# LoRaWAN_FW_RevB.net
KiCad netlist of a schematic drawn in EAGLE
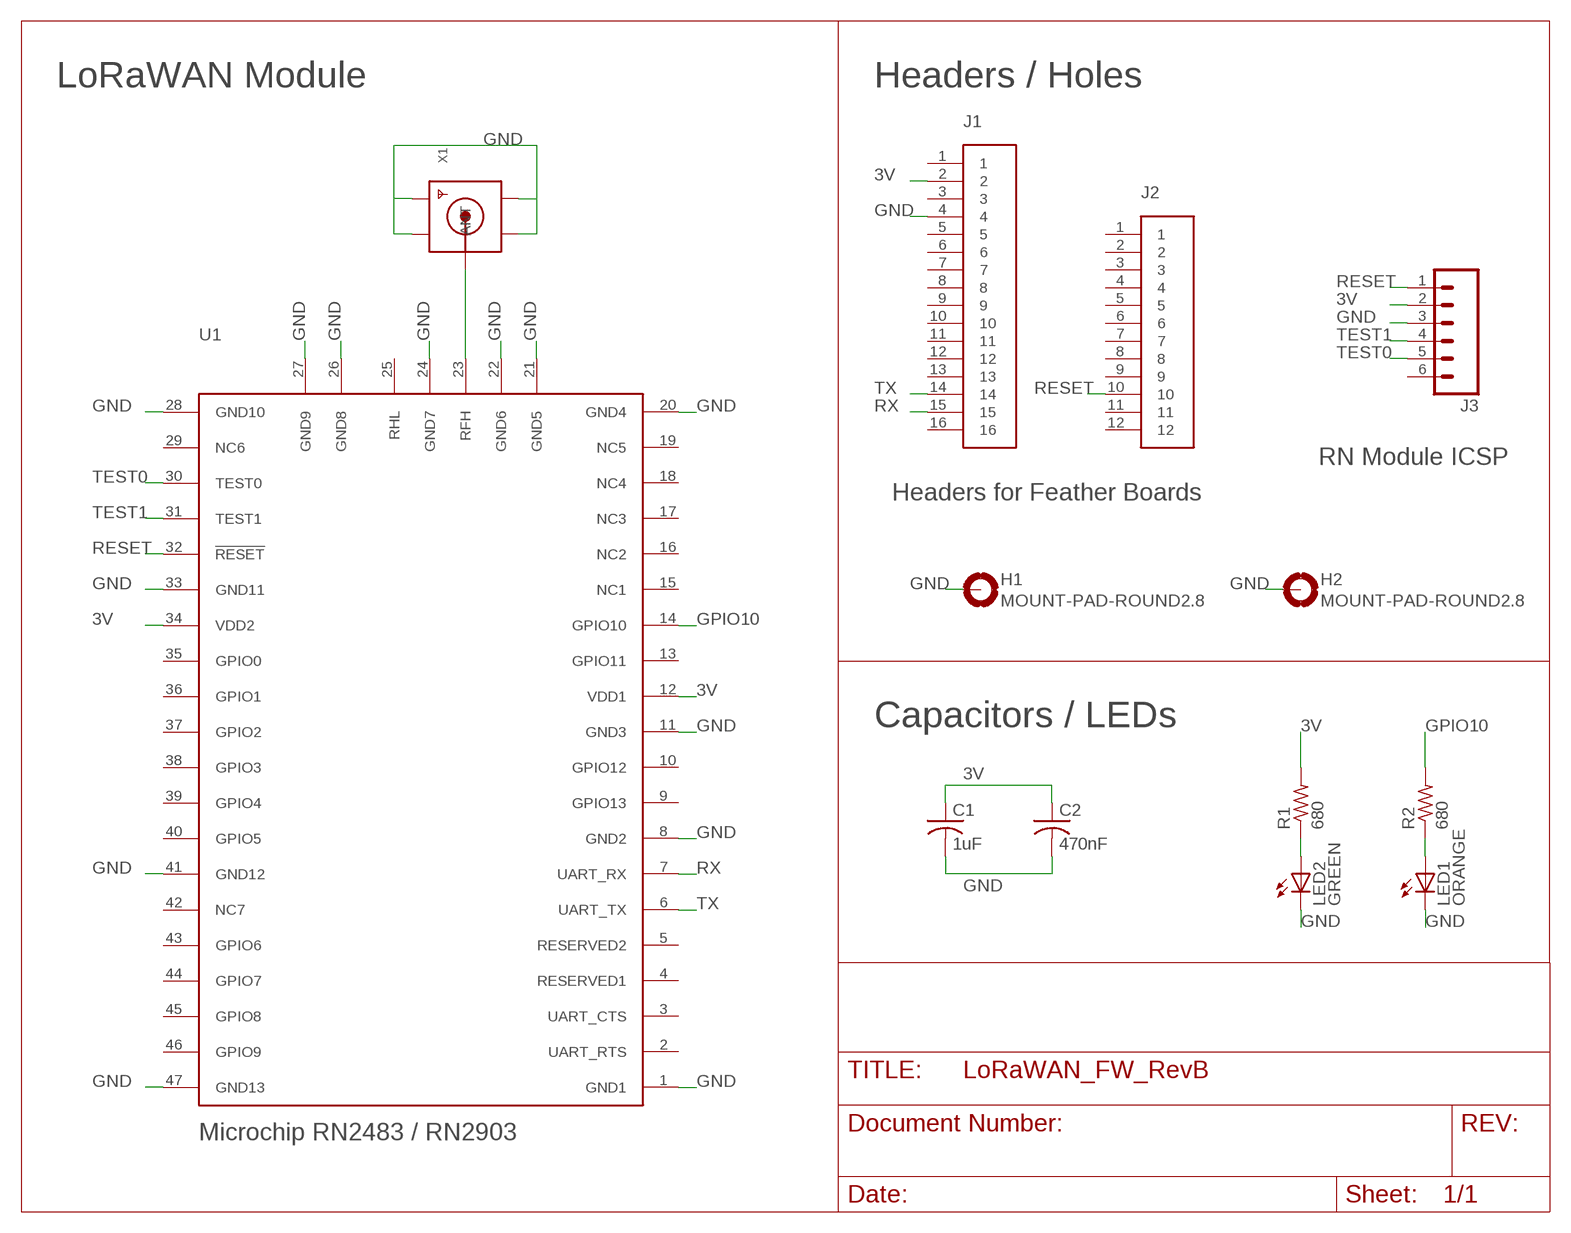
[diagram p0: schematic, sheet 1]

(export (version "E")
  (design (tool "Eeschema 10.0.6"))
  (components
    (comp (ref "C1")
      (value "1uF")
      (footprint "eagle-import:C0603")
      (libsource (lib "eagle-import") (part "C-USC0603"))
    )
    (comp (ref "C2")
      (value "470nF")
      (footprint "eagle-import:C0603")
      (libsource (lib "eagle-import") (part "C-USC0603"))
    )
    (comp (ref "H1")
      (value "MOUNT-PAD-ROUND2.8")
      (footprint "eagle-import:2,8-PAD")
      (libsource (lib "eagle-import") (part "MOUNT-PAD-ROUND2.8"))
    )
    (comp (ref "H2")
      (value "MOUNT-PAD-ROUND2.8")
      (footprint "eagle-import:2,8-PAD")
      (libsource (lib "eagle-import") (part "MOUNT-PAD-ROUND2.8"))
    )
    (comp (ref "J1")
      (value "1X16_SMD_HEADER")
      (footprint "eagle-import:1X16_SMD_HEADER")
      (libsource (lib "eagle-import") (part "1X16_SMD_HEADER"))
    )
    (comp (ref "J2")
      (value "1X12_SMD_HEADER")
      (footprint "eagle-import:1X12_SMD_HEADER")
      (libsource (lib "eagle-import") (part "1X12_SMD_HEADER"))
    )
    (comp (ref "J3")
      (value "M06SILK_FEMALE_PTH")
      (footprint "eagle-import:1X06")
      (libsource (lib "eagle-import") (part "M06SILK_FEMALE_PTH"))
    )
    (comp (ref "LED1")
      (value "ORANGE")
      (footprint "eagle-import:CHIPLED_0805")
      (libsource (lib "eagle-import") (part "LEDCHIPLED_0805"))
    )
    (comp (ref "LED2")
      (value "GREEN")
      (footprint "eagle-import:CHIPLED_0805")
      (libsource (lib "eagle-import") (part "LEDCHIPLED_0805"))
    )
    (comp (ref "R1")
      (value "680")
      (footprint "eagle-import:R0603")
      (libsource (lib "eagle-import") (part "R-US_R0603"))
    )
    (comp (ref "R2")
      (value "680")
      (footprint "eagle-import:R0603")
      (libsource (lib "eagle-import") (part "R-US_R0603"))
    )
    (comp (ref "U1")
      (value "RN2483/RN2903")
      (footprint "eagle-import:RN2483_RN2903")
      (libsource (lib "eagle-import") (part "RN2483/RN2903"))
    )
    (comp (ref "X1")
      (value "SMACONNECTOR_EDGE")
      (footprint "eagle-import:SMA_EDGELAUNCH")
      (libsource (lib "eagle-import") (part "SMACONNECTOR_EDGE"))
    )
  )
  (nets
    (net (code "1") (name "/3V") (class "Default")
      (node (ref "C1") (pin "1") (pinfunction "1_1") (pintype "passive"))
      (node (ref "C2") (pin "1") (pinfunction "1_1") (pintype "passive"))
      (node (ref "J1") (pin "2") (pinfunction "2_2") (pintype "bidirectional"))
      (node (ref "J3") (pin "2") (pinfunction "2_2") (pintype "passive"))
      (node (ref "R1") (pin "2") (pinfunction "2_2") (pintype "passive"))
      (node (ref "U1") (pin "12") (pinfunction "VDD1_12") (pintype "bidirectional"))
      (node (ref "U1") (pin "34") (pinfunction "VDD2_34") (pintype "bidirectional"))
    )
    (net (code "2") (name "/GND") (class "Default")
      (node (ref "C1") (pin "2") (pinfunction "2_2") (pintype "passive"))
      (node (ref "C2") (pin "2") (pinfunction "2_2") (pintype "passive"))
      (node (ref "H1") (pin "B2,8") (pinfunction "MOUNT_B2,8") (pintype "passive"))
      (node (ref "H2") (pin "B2,8") (pinfunction "MOUNT_B2,8") (pintype "passive"))
      (node (ref "J1") (pin "4") (pinfunction "4_4") (pintype "bidirectional"))
      (node (ref "J3") (pin "3") (pinfunction "3_3") (pintype "passive"))
      (node (ref "LED1") (pin "C") (pinfunction "C_C") (pintype "passive"))
      (node (ref "LED2") (pin "C") (pinfunction "C_C") (pintype "passive"))
      (node (ref "U1") (pin "1") (pinfunction "GND1_1") (pintype "bidirectional"))
      (node (ref "U1") (pin "11") (pinfunction "GND3_11") (pintype "bidirectional"))
      (node (ref "U1") (pin "20") (pinfunction "GND4_20") (pintype "bidirectional"))
      (node (ref "U1") (pin "21") (pinfunction "GND5_21") (pintype "bidirectional"))
      (node (ref "U1") (pin "22") (pinfunction "GND6_22") (pintype "bidirectional"))
      (node (ref "U1") (pin "24") (pinfunction "GND7_24") (pintype "bidirectional"))
      (node (ref "U1") (pin "26") (pinfunction "GND8_26") (pintype "bidirectional"))
      (node (ref "U1") (pin "27") (pinfunction "GND9_27") (pintype "bidirectional"))
      (node (ref "U1") (pin "28") (pinfunction "GND10_28") (pintype "bidirectional"))
      (node (ref "U1") (pin "33") (pinfunction "GND11_33") (pintype "bidirectional"))
      (node (ref "U1") (pin "41") (pinfunction "GND12_41") (pintype "bidirectional"))
      (node (ref "U1") (pin "47") (pinfunction "GND13_47") (pintype "bidirectional"))
      (node (ref "U1") (pin "8") (pinfunction "GND2_8") (pintype "bidirectional"))
      (node (ref "X1") (pin "GND@1") (pinfunction "GND4_GND@1") (pintype "power_in"))
      (node (ref "X1") (pin "GND@2") (pinfunction "GND3_GND@2") (pintype "power_in"))
      (node (ref "X1") (pin "GND@3") (pinfunction "GND2_GND@3") (pintype "power_in"))
      (node (ref "X1") (pin "GND@4") (pinfunction "GND1_GND@4") (pintype "power_in"))
    )
    (net (code "3") (name "/GPIO10") (class "Default")
      (node (ref "R2") (pin "2") (pinfunction "2_2") (pintype "passive"))
      (node (ref "U1") (pin "14") (pinfunction "GPIO10_14") (pintype "bidirectional"))
    )
    (net (code "4") (name "/RESET") (class "Default")
      (node (ref "J2") (pin "10") (pinfunction "10_10") (pintype "bidirectional"))
      (node (ref "J3") (pin "1") (pinfunction "1_1") (pintype "passive"))
      (node (ref "U1") (pin "32") (pinfunction "~{RESET}_32") (pintype "bidirectional"))
    )
    (net (code "5") (name "/RX") (class "Default")
      (node (ref "J1") (pin "15") (pinfunction "15_15") (pintype "bidirectional"))
      (node (ref "U1") (pin "7") (pinfunction "UART_RX_7") (pintype "bidirectional"))
    )
    (net (code "6") (name "/TEST0") (class "Default")
      (node (ref "J3") (pin "5") (pinfunction "5_5") (pintype "passive"))
      (node (ref "U1") (pin "30") (pinfunction "TEST0_30") (pintype "bidirectional"))
    )
    (net (code "7") (name "/TEST1") (class "Default")
      (node (ref "J3") (pin "4") (pinfunction "4_4") (pintype "passive"))
      (node (ref "U1") (pin "31") (pinfunction "TEST1_31") (pintype "bidirectional"))
    )
    (net (code "8") (name "/TX") (class "Default")
      (node (ref "J1") (pin "14") (pinfunction "14_14") (pintype "bidirectional"))
      (node (ref "U1") (pin "6") (pinfunction "UART_TX_6") (pintype "bidirectional"))
    )
    (net (code "9") (name "Net-(LED1-PadA)") (class "Default")
      (node (ref "LED1") (pin "A") (pinfunction "A_A") (pintype "passive"))
      (node (ref "R2") (pin "1") (pinfunction "1_1") (pintype "passive"))
    )
    (net (code "10") (name "Net-(LED2-PadA)") (class "Default")
      (node (ref "LED2") (pin "A") (pinfunction "A_A") (pintype "passive"))
      (node (ref "R1") (pin "1") (pinfunction "1_1") (pintype "passive"))
    )
    (net (code "11") (name "Net-(U1-RFH)") (class "Default")
      (node (ref "U1") (pin "23") (pinfunction "RFH_23") (pintype "bidirectional"))
      (node (ref "X1") (pin "P") (pinfunction "ANT_P") (pintype "bidirectional"))
    )
    (net (code "12") (name "unconnected-(J1-Pad1)") (class "Default")
      (node (ref "J1") (pin "1") (pinfunction "1_1") (pintype "bidirectional"))
    )
    (net (code "13") (name "unconnected-(J1-Pad3)") (class "Default")
      (node (ref "J1") (pin "3") (pinfunction "3_3") (pintype "bidirectional"))
    )
    (net (code "14") (name "unconnected-(J1-Pad5)") (class "Default")
      (node (ref "J1") (pin "5") (pinfunction "5_5") (pintype "bidirectional"))
    )
    (net (code "15") (name "unconnected-(J1-Pad6)") (class "Default")
      (node (ref "J1") (pin "6") (pinfunction "6_6") (pintype "bidirectional"))
    )
    (net (code "16") (name "unconnected-(J1-Pad7)") (class "Default")
      (node (ref "J1") (pin "7") (pinfunction "7_7") (pintype "bidirectional"))
    )
    (net (code "17") (name "unconnected-(J1-Pad8)") (class "Default")
      (node (ref "J1") (pin "8") (pinfunction "8_8") (pintype "bidirectional"))
    )
    (net (code "18") (name "unconnected-(J1-Pad9)") (class "Default")
      (node (ref "J1") (pin "9") (pinfunction "9_9") (pintype "bidirectional"))
    )
    (net (code "19") (name "unconnected-(J1-Pad10)") (class "Default")
      (node (ref "J1") (pin "10") (pinfunction "10_10") (pintype "bidirectional"))
    )
    (net (code "20") (name "unconnected-(J1-Pad11)") (class "Default")
      (node (ref "J1") (pin "11") (pinfunction "11_11") (pintype "bidirectional"))
    )
    (net (code "21") (name "unconnected-(J1-Pad12)") (class "Default")
      (node (ref "J1") (pin "12") (pinfunction "12_12") (pintype "bidirectional"))
    )
    (net (code "22") (name "unconnected-(J1-Pad13)") (class "Default")
      (node (ref "J1") (pin "13") (pinfunction "13_13") (pintype "bidirectional"))
    )
    (net (code "23") (name "unconnected-(J1-Pad16)") (class "Default")
      (node (ref "J1") (pin "16") (pinfunction "16_16") (pintype "bidirectional"))
    )
    (net (code "24") (name "unconnected-(J2-Pad1)") (class "Default")
      (node (ref "J2") (pin "1") (pinfunction "1_1") (pintype "bidirectional"))
    )
    (net (code "25") (name "unconnected-(J2-Pad2)") (class "Default")
      (node (ref "J2") (pin "2") (pinfunction "2_2") (pintype "bidirectional"))
    )
    (net (code "26") (name "unconnected-(J2-Pad3)") (class "Default")
      (node (ref "J2") (pin "3") (pinfunction "3_3") (pintype "bidirectional"))
    )
    (net (code "27") (name "unconnected-(J2-Pad4)") (class "Default")
      (node (ref "J2") (pin "4") (pinfunction "4_4") (pintype "bidirectional"))
    )
    (net (code "28") (name "unconnected-(J2-Pad5)") (class "Default")
      (node (ref "J2") (pin "5") (pinfunction "5_5") (pintype "bidirectional"))
    )
    (net (code "29") (name "unconnected-(J2-Pad6)") (class "Default")
      (node (ref "J2") (pin "6") (pinfunction "6_6") (pintype "bidirectional"))
    )
    (net (code "30") (name "unconnected-(J2-Pad7)") (class "Default")
      (node (ref "J2") (pin "7") (pinfunction "7_7") (pintype "bidirectional"))
    )
    (net (code "31") (name "unconnected-(J2-Pad8)") (class "Default")
      (node (ref "J2") (pin "8") (pinfunction "8_8") (pintype "bidirectional"))
    )
    (net (code "32") (name "unconnected-(J2-Pad9)") (class "Default")
      (node (ref "J2") (pin "9") (pinfunction "9_9") (pintype "bidirectional"))
    )
    (net (code "33") (name "unconnected-(J2-Pad11)") (class "Default")
      (node (ref "J2") (pin "11") (pinfunction "11_11") (pintype "bidirectional"))
    )
    (net (code "34") (name "unconnected-(J2-Pad12)") (class "Default")
      (node (ref "J2") (pin "12") (pinfunction "12_12") (pintype "bidirectional"))
    )
    (net (code "35") (name "unconnected-(J3-Pad6)") (class "Default")
      (node (ref "J3") (pin "6") (pinfunction "6_6") (pintype "passive"))
    )
    (net (code "36") (name "unconnected-(U1-GPIO0-Pad35)") (class "Default")
      (node (ref "U1") (pin "35") (pinfunction "GPIO0_35") (pintype "bidirectional"))
    )
    (net (code "37") (name "unconnected-(U1-GPIO1-Pad36)") (class "Default")
      (node (ref "U1") (pin "36") (pinfunction "GPIO1_36") (pintype "bidirectional"))
    )
    (net (code "38") (name "unconnected-(U1-GPIO2-Pad37)") (class "Default")
      (node (ref "U1") (pin "37") (pinfunction "GPIO2_37") (pintype "bidirectional"))
    )
    (net (code "39") (name "unconnected-(U1-GPIO3-Pad38)") (class "Default")
      (node (ref "U1") (pin "38") (pinfunction "GPIO3_38") (pintype "bidirectional"))
    )
    (net (code "40") (name "unconnected-(U1-GPIO4-Pad39)") (class "Default")
      (node (ref "U1") (pin "39") (pinfunction "GPIO4_39") (pintype "bidirectional"))
    )
    (net (code "41") (name "unconnected-(U1-GPIO5-Pad40)") (class "Default")
      (node (ref "U1") (pin "40") (pinfunction "GPIO5_40") (pintype "bidirectional"))
    )
    (net (code "42") (name "unconnected-(U1-GPIO6-Pad43)") (class "Default")
      (node (ref "U1") (pin "43") (pinfunction "GPIO6_43") (pintype "bidirectional"))
    )
    (net (code "43") (name "unconnected-(U1-GPIO7-Pad44)") (class "Default")
      (node (ref "U1") (pin "44") (pinfunction "GPIO7_44") (pintype "bidirectional"))
    )
    (net (code "44") (name "unconnected-(U1-GPIO8-Pad45)") (class "Default")
      (node (ref "U1") (pin "45") (pinfunction "GPIO8_45") (pintype "bidirectional"))
    )
    (net (code "45") (name "unconnected-(U1-GPIO9-Pad46)") (class "Default")
      (node (ref "U1") (pin "46") (pinfunction "GPIO9_46") (pintype "bidirectional"))
    )
    (net (code "46") (name "unconnected-(U1-GPIO11-Pad13)") (class "Default")
      (node (ref "U1") (pin "13") (pinfunction "GPIO11_13") (pintype "bidirectional"))
    )
    (net (code "47") (name "unconnected-(U1-GPIO12-Pad10)") (class "Default")
      (node (ref "U1") (pin "10") (pinfunction "GPIO12_10") (pintype "bidirectional"))
    )
    (net (code "48") (name "unconnected-(U1-GPIO13-Pad9)") (class "Default")
      (node (ref "U1") (pin "9") (pinfunction "GPIO13_9") (pintype "bidirectional"))
    )
    (net (code "49") (name "unconnected-(U1-NC1-Pad15)") (class "Default")
      (node (ref "U1") (pin "15") (pinfunction "NC1_15") (pintype "bidirectional"))
    )
    (net (code "50") (name "unconnected-(U1-NC2-Pad16)") (class "Default")
      (node (ref "U1") (pin "16") (pinfunction "NC2_16") (pintype "bidirectional"))
    )
    (net (code "51") (name "unconnected-(U1-NC3-Pad17)") (class "Default")
      (node (ref "U1") (pin "17") (pinfunction "NC3_17") (pintype "bidirectional"))
    )
    (net (code "52") (name "unconnected-(U1-NC4-Pad18)") (class "Default")
      (node (ref "U1") (pin "18") (pinfunction "NC4_18") (pintype "bidirectional"))
    )
    (net (code "53") (name "unconnected-(U1-NC5-Pad19)") (class "Default")
      (node (ref "U1") (pin "19") (pinfunction "NC5_19") (pintype "bidirectional"))
    )
    (net (code "54") (name "unconnected-(U1-NC6-Pad29)") (class "Default")
      (node (ref "U1") (pin "29") (pinfunction "NC6_29") (pintype "bidirectional"))
    )
    (net (code "55") (name "unconnected-(U1-NC7-Pad42)") (class "Default")
      (node (ref "U1") (pin "42") (pinfunction "NC7_42") (pintype "bidirectional"))
    )
    (net (code "56") (name "unconnected-(U1-RESERVED1-Pad4)") (class "Default")
      (node (ref "U1") (pin "4") (pinfunction "RESERVED1_4") (pintype "bidirectional"))
    )
    (net (code "57") (name "unconnected-(U1-RESERVED2-Pad5)") (class "Default")
      (node (ref "U1") (pin "5") (pinfunction "RESERVED2_5") (pintype "bidirectional"))
    )
    (net (code "58") (name "unconnected-(U1-RHL-Pad25)") (class "Default")
      (node (ref "U1") (pin "25") (pinfunction "RHL_25") (pintype "bidirectional"))
    )
    (net (code "59") (name "unconnected-(U1-UART_CTS-Pad3)") (class "Default")
      (node (ref "U1") (pin "3") (pinfunction "UART_CTS_3") (pintype "bidirectional"))
    )
    (net (code "60") (name "unconnected-(U1-UART_RTS-Pad2)") (class "Default")
      (node (ref "U1") (pin "2") (pinfunction "UART_RTS_2") (pintype "bidirectional"))
    )
  )
)
